# MainIC.net
KiCad netlist of a schematic drawn in Altium Designer
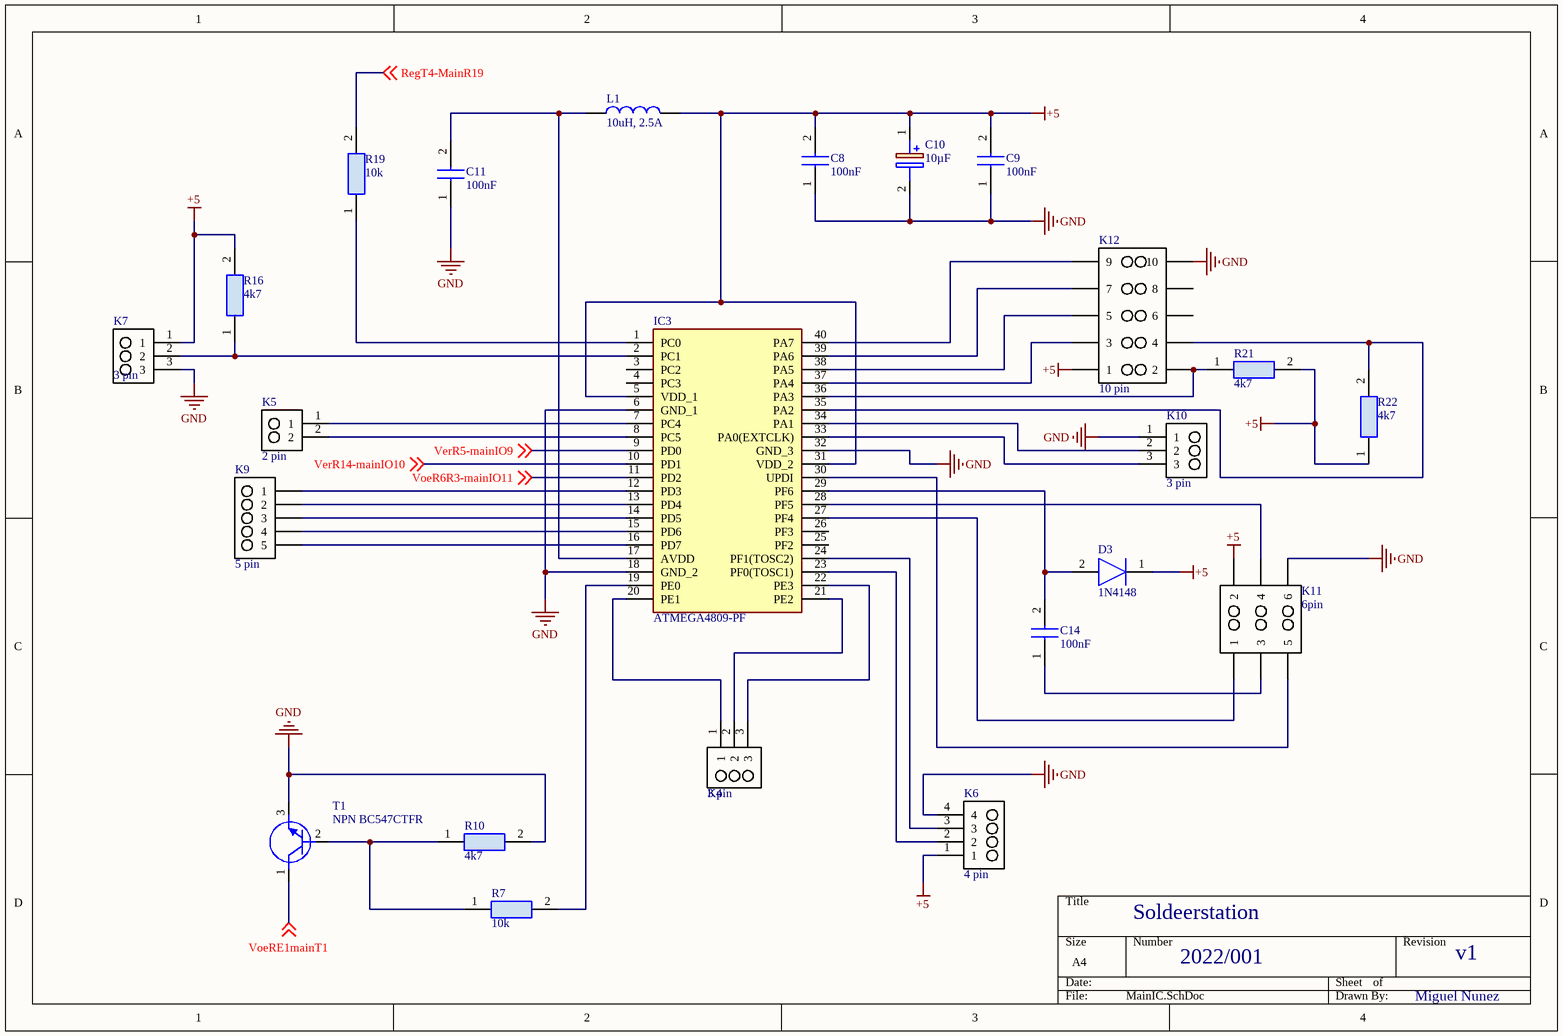
[diagram p0: MainIC.SchDoc]

(export (version "E")
  (design (tool "Eeschema 10.0.6"))
  (components
    (comp (ref "C8")
      (value "100nF")
      (footprint "WCAP-CSGP_0805_L2W1.25H0.8_Reflow")
      (description "Capacitor C0805C104K8RACAUTO")
      (fields (field (name "MANUFACTURER_PART_NUMBER") "C0805C104K8RACAUTO"))
      (libsource (lib "PO_SS_Lib") (part "CAP 0.1µF (100nF)"))
    )
    (comp (ref "C9")
      (value "100nF")
      (footprint "WCAP-CSGP_0805_L2W1.25H0.8_Reflow")
      (description "Capacitor C0805C104K8RACAUTO")
      (fields (field (name "MANUFACTURER_PART_NUMBER") "C0805C104K8RACAUTO"))
      (libsource (lib "PO_SS_Lib") (part "CAP 0.1µF (100nF)"))
    )
    (comp (ref "C10")
      (value "10µF")
      (footprint "WCAP-AT1H_D5H11")
      (description "Capacitor Polarised Wurth Elektronik 860240672002 10µF")
      (fields (field (name "MANUFACTURER_PART_NUMBER") "860240672002"))
      (libsource (lib "PO_SS_Lib") (part "ELCAP 10µF"))
    )
    (comp (ref "C11")
      (value "100nF")
      (footprint "WCAP-CSGP_0805_L2W1.25H0.8_Reflow")
      (description "Capacitor C0805C104K8RACAUTO")
      (fields (field (name "MANUFACTURER_PART_NUMBER") "C0805C104K8RACAUTO"))
      (libsource (lib "PO_SS_Lib") (part "CAP 0.1µF (100nF)"))
    )
    (comp (ref "C14")
      (value "100nF")
      (footprint "WCAP-CSGP_0805_L2W1.25H0.8_Reflow")
      (description "Capacitor C0805C104K8RACAUTO")
      (fields (field (name "MANUFACTURER_PART_NUMBER") "C0805C104K8RACAUTO"))
      (libsource (lib "PO_SS_Lib") (part "CAP 0.1µF (100nF)"))
    )
    (comp (ref "D3")
      (value "1N4148")
      (footprint "SamacSys:DIOAD1165W56L425D185")
      (description "Diode 1N4148 100V, 200mA")
      (libsource (lib "PO_SS_Lib") (part "D 1N4148"))
    )
    (comp (ref "IC3")
      (value "ATMEGA4809-PF")
      (footprint "SamacSys:DIP1543W58P254L5175H635Q40N")
      (description "Integrated Circuit")
      (fields (field (name "MOUSER2 PART NUMBER") "556-ATMEGA4809-PF"))
      (libsource (lib "PO_SS_Lib") (part "ATMEGA4809-PF"))
    )
    (comp (ref "K4")
      (value "3 pin")
      (footprint "691214310003")
      (description "Connector 61900311121 3 pin")
      (fields (field (name "MANUFACTURER_PART_NUMBER") "61900311121"))
      (libsource (lib "") (part "Header 1x3pin_2"))
    )
    (comp (ref "K5")
      (value "2 pin")
      (footprint "691214110002")
      (description "Connector 2 pin 212520-1002")
      (fields (field (name "MANUFACTURER_PART_NUMBER") "212520-1002"))
      (libsource (lib "PO_SS_Lib") (part "Header 1x2pin"))
    )
    (comp (ref "K6")
      (value "4 pin")
      (footprint "SHDR4W78P0X254_1X4_1026X252X700P")
      (description "Connector 216571-3004 1x4 pin")
      (fields (field (name "MANUFACTURER_PART_NUMBER") "216571-3004"))
      (libsource (lib "PO_SS_Lib") (part "Header 1x4pin"))
    )
    (comp (ref "K7")
      (value "3 pin")
      (footprint "691214310003")
      (description "Connector 61900311121 3 pin")
      (fields (field (name "MANUFACTURER_PART_NUMBER") "61900311121"))
      (libsource (lib "") (part "Header 1x3pin_1"))
    )
    (comp (ref "K9")
      (value "5 pin")
      (footprint "215297-5_TYC")
      (description "Header, 5-Pin")
      (fields (field (name "PUBLISHER") "Altium Limited"))
      (libsource (lib "PO_SS_Lib") (part "Header 1x 5pin"))
    )
    (comp (ref "K10")
      (value "3 pin")
      (footprint "691214310003")
      (description "Connector 61900311121 3 pin")
      (fields (field (name "MANUFACTURER_PART_NUMBER") "61900311121"))
      (libsource (lib "PO_SS_Lib") (part "Header 1x3pin"))
    )
    (comp (ref "K11")
      (value "6pin")
      (footprint "215307-3_TYC")
      (description "Header, 3-Pin, Dual row")
      (fields (field (name "PUBLISHER") "Altium Limited"))
      (libsource (lib "PO_SS_Lib") (part "Header 2x3"))
    )
    (comp (ref "K12")
      (value "10 pin")
      (footprint "215307-5_TYC")
      (description "Header, 5-Pin, Dual row")
      (fields (field (name "PUBLISHER") "Altium Limited"))
      (libsource (lib "PO_SS_Lib") (part "Header 2x5"))
    )
    (comp (ref "L1")
      (value "10uH, 2.5A")
      (footprint "744711003")
      (description "WE-SD THT Rod Core Choke, 10uH, 2.5A  744711003")
      (fields
        (field (name "MANUFACTURER PART NUMBER") "744711003")
        (field (name "MANUFACTURER") "Wurth Elektronik")
      )
      (libsource (lib "PO_SS_Lib") (part "spoel WE klein"))
    )
    (comp (ref "R7")
      (value "10k")
      (footprint "SamacSys:RESC2012X60N")
      (description "10k SMD 0805  CR0805-FX-1002ELF")
      (fields
        (field (name "MOUSER2 PART NUMBER") "652-CR0805FX-1002ELF")
        (field (name "MANUFACTURER_PART_NUMBER") "CR0805-FX-1002ELF")
      )
      (libsource (lib "") (part "RES 10k 0805_1"))
    )
    (comp (ref "R10")
      (value "4k7")
      (footprint "SamacSys:CAPC2012X65N")
      (description "4k7 SMD 0805  ESR10EZPJ472")
      (fields (field (name "MANUFACTURER_PART_NUMBER") "ESR10EZPJ472"))
      (libsource (lib "") (part "RES 4k7 0805_1"))
    )
    (comp (ref "R16")
      (value "4k7")
      (footprint "SamacSys:CAPC2012X65N")
      (description "4k7 SMD 0805  ESR10EZPJ472")
      (fields (field (name "MANUFACTURER_PART_NUMBER") "ESR10EZPJ472"))
      (libsource (lib "PO_SS_Lib") (part "RES 4k7 0805"))
    )
    (comp (ref "R19")
      (value "10k")
      (footprint "SamacSys:RESC2012X60N")
      (description "10k SMD 0805  CR0805-FX-1002ELF")
      (fields
        (field (name "MOUSER2 PART NUMBER") "652-CR0805FX-1002ELF")
        (field (name "MANUFACTURER_PART_NUMBER") "CR0805-FX-1002ELF")
      )
      (libsource (lib "PO_SS_Lib") (part "RES 10k 0805"))
    )
    (comp (ref "R21")
      (value "4k7")
      (footprint "SamacSys:CAPC2012X65N")
      (description "4k7 SMD 0805  ESR10EZPJ472")
      (fields (field (name "MANUFACTURER_PART_NUMBER") "ESR10EZPJ472"))
      (libsource (lib "") (part "RES 4k7 0805_1"))
    )
    (comp (ref "R22")
      (value "4k7")
      (footprint "SamacSys:CAPC2012X65N")
      (description "4k7 SMD 0805  ESR10EZPJ472")
      (fields (field (name "MANUFACTURER_PART_NUMBER") "ESR10EZPJ472"))
      (libsource (lib "PO_SS_Lib") (part "RES 4k7 0805"))
    )
    (comp (ref "T1")
      (value "NPN BC547CTFR")
      (footprint "BC33740TA")
      (description "Transistor BC547CTFR NPN")
      (fields
        (field (name "MANUFACTURER_PART_NUMBER") "BC547CTFR")
        (field (name "COPYRIGHT") "Copyright (C) 2022 Ultra Librarian. All rights reserved.")
      )
      (libsource (lib "PO_SS_Lib") (part "TR BC547CTFR"))
    )
  )
  (nets
    (net (code "1") (name "+5") (class "Default")
      (node (ref "C10") (pin "1") (pinfunction "+_1") (pintype "passive"))
      (node (ref "C8") (pin "2") (pinfunction "2_2") (pintype "passive"))
      (node (ref "C9") (pin "2") (pinfunction "2_2") (pintype "passive"))
      (node (ref "D3") (pin "1") (pinfunction "K_1") (pintype "passive"))
      (node (ref "IC3") (pin "31") (pinfunction "VDD_2_31") (pintype "passive"))
      (node (ref "IC3") (pin "5") (pinfunction "VDD_1_5") (pintype "passive"))
      (node (ref "K11") (pin "2") (pinfunction "2_2") (pintype "passive"))
      (node (ref "K12") (pin "1") (pinfunction "1_1") (pintype "passive"))
      (node (ref "K6") (pin "1") (pinfunction "1_1") (pintype "passive"))
      (node (ref "K7") (pin "1") (pinfunction "1_1") (pintype "passive"))
      (node (ref "L1") (pin "2") (pinfunction "2_2") (pintype "passive"))
      (node (ref "R16") (pin "2") (pinfunction "2_2") (pintype "passive"))
      (node (ref "R21") (pin "2") (pinfunction "2_2") (pintype "passive"))
      (node (ref "R22") (pin "1") (pinfunction "1_1") (pintype "passive"))
    )
    (net (code "2") (name "GND") (class "Default")
      (node (ref "C10") (pin "2") (pinfunction "-_2") (pintype "passive"))
      (node (ref "C11") (pin "1") (pinfunction "1_1") (pintype "passive"))
      (node (ref "C8") (pin "1") (pinfunction "1_1") (pintype "passive"))
      (node (ref "C9") (pin "1") (pinfunction "1_1") (pintype "passive"))
      (node (ref "IC3") (pin "18") (pinfunction "GND_2_18") (pintype "passive"))
      (node (ref "IC3") (pin "32") (pinfunction "GND_3_32") (pintype "passive"))
      (node (ref "IC3") (pin "6") (pinfunction "GND_1_6") (pintype "passive"))
      (node (ref "K10") (pin "1") (pinfunction "1_1") (pintype "passive"))
      (node (ref "K11") (pin "6") (pinfunction "6_6") (pintype "passive"))
      (node (ref "K12") (pin "10") (pinfunction "10_10") (pintype "passive"))
      (node (ref "K6") (pin "4") (pinfunction "4_4") (pintype "passive"))
      (node (ref "K7") (pin "3") (pinfunction "3_3") (pintype "passive"))
      (node (ref "R10") (pin "2") (pinfunction "2_2") (pintype "passive"))
      (node (ref "T1") (pin "3") (pinfunction "E_3") (pintype "passive"))
    )
    (net (code "3") (name "Net-(C14-Pad1)") (class "Default")
      (node (ref "C14") (pin "1") (pinfunction "1_1") (pintype "passive"))
      (node (ref "K11") (pin "3") (pinfunction "3_3") (pintype "passive"))
    )
    (net (code "4") (name "Net-(D3-A)") (class "Default")
      (node (ref "C14") (pin "2") (pinfunction "2_2") (pintype "passive"))
      (node (ref "D3") (pin "2") (pinfunction "A_2") (pintype "passive"))
      (node (ref "IC3") (pin "29") (pinfunction "PF6_29") (pintype "passive"))
    )
    (net (code "5") (name "Net-(IC3-AVDD)") (class "Default")
      (node (ref "C11") (pin "2") (pinfunction "2_2") (pintype "passive"))
      (node (ref "IC3") (pin "17") (pinfunction "AVDD_17") (pintype "passive"))
      (node (ref "L1") (pin "1") (pinfunction "1_1") (pintype "passive"))
    )
    (net (code "6") (name "Net-(IC3-PA0(EXTCLK))") (class "Default")
      (node (ref "IC3") (pin "33") (pinfunction "PA0(EXTCLK)_33") (pintype "passive"))
      (node (ref "K10") (pin "3") (pinfunction "3_3") (pintype "passive"))
    )
    (net (code "7") (name "Net-(IC3-PA1)") (class "Default")
      (node (ref "IC3") (pin "34") (pinfunction "PA1_34") (pintype "passive"))
      (node (ref "K10") (pin "2") (pinfunction "2_2") (pintype "passive"))
    )
    (net (code "8") (name "Net-(IC3-PA2)") (class "Default")
      (node (ref "IC3") (pin "35") (pinfunction "PA2_35") (pintype "passive"))
      (node (ref "K12") (pin "4") (pinfunction "4_4") (pintype "passive"))
      (node (ref "R22") (pin "2") (pinfunction "2_2") (pintype "passive"))
    )
    (net (code "9") (name "Net-(IC3-PA3)") (class "Default")
      (node (ref "IC3") (pin "36") (pinfunction "PA3_36") (pintype "passive"))
      (node (ref "K12") (pin "2") (pinfunction "2_2") (pintype "passive"))
      (node (ref "R21") (pin "1") (pinfunction "1_1") (pintype "passive"))
    )
    (net (code "10") (name "Net-(IC3-PA4)") (class "Default")
      (node (ref "IC3") (pin "37") (pinfunction "PA4_37") (pintype "passive"))
      (node (ref "K12") (pin "3") (pinfunction "3_3") (pintype "passive"))
    )
    (net (code "11") (name "Net-(IC3-PA5)") (class "Default")
      (node (ref "IC3") (pin "38") (pinfunction "PA5_38") (pintype "passive"))
      (node (ref "K12") (pin "5") (pinfunction "5_5") (pintype "passive"))
    )
    (net (code "12") (name "Net-(IC3-PA6)") (class "Default")
      (node (ref "IC3") (pin "39") (pinfunction "PA6_39") (pintype "passive"))
      (node (ref "K12") (pin "7") (pinfunction "7_7") (pintype "passive"))
    )
    (net (code "13") (name "Net-(IC3-PA7)") (class "Default")
      (node (ref "IC3") (pin "40") (pinfunction "PA7_40") (pintype "passive"))
      (node (ref "K12") (pin "9") (pinfunction "9_9") (pintype "passive"))
    )
    (net (code "14") (name "Net-(IC3-PC0)") (class "Default")
      (node (ref "IC3") (pin "1") (pinfunction "PC0_1") (pintype "passive"))
      (node (ref "R19") (pin "1") (pinfunction "1_1") (pintype "passive"))
    )
    (net (code "15") (name "Net-(IC3-PC1)") (class "Default")
      (node (ref "IC3") (pin "2") (pinfunction "PC1_2") (pintype "passive"))
      (node (ref "K7") (pin "2") (pinfunction "2_2") (pintype "passive"))
      (node (ref "R16") (pin "1") (pinfunction "1_1") (pintype "passive"))
    )
    (net (code "16") (name "Net-(IC3-PC4)") (class "Default")
      (node (ref "IC3") (pin "7") (pinfunction "PC4_7") (pintype "passive"))
      (node (ref "K5") (pin "1") (pinfunction "1_1") (pintype "passive"))
    )
    (net (code "17") (name "Net-(IC3-PC5)") (class "Default")
      (node (ref "IC3") (pin "8") (pinfunction "PC5_8") (pintype "passive"))
      (node (ref "K5") (pin "2") (pinfunction "2_2") (pintype "passive"))
    )
    (net (code "18") (name "Net-(IC3-PD3)") (class "Default")
      (node (ref "IC3") (pin "12") (pinfunction "PD3_12") (pintype "passive"))
      (node (ref "K9") (pin "1") (pinfunction "1_1") (pintype "passive"))
    )
    (net (code "19") (name "Net-(IC3-PD4)") (class "Default")
      (node (ref "IC3") (pin "13") (pinfunction "PD4_13") (pintype "passive"))
      (node (ref "K9") (pin "2") (pinfunction "2_2") (pintype "passive"))
    )
    (net (code "20") (name "Net-(IC3-PD5)") (class "Default")
      (node (ref "IC3") (pin "14") (pinfunction "PD5_14") (pintype "passive"))
      (node (ref "K9") (pin "3") (pinfunction "3_3") (pintype "passive"))
    )
    (net (code "21") (name "Net-(IC3-PD6)") (class "Default")
      (node (ref "IC3") (pin "15") (pinfunction "PD6_15") (pintype "passive"))
      (node (ref "K9") (pin "4") (pinfunction "4_4") (pintype "passive"))
    )
    (net (code "22") (name "Net-(IC3-PD7)") (class "Default")
      (node (ref "IC3") (pin "16") (pinfunction "PD7_16") (pintype "passive"))
      (node (ref "K9") (pin "5") (pinfunction "5_5") (pintype "passive"))
    )
    (net (code "23") (name "Net-(IC3-PE0)") (class "Default")
      (node (ref "IC3") (pin "19") (pinfunction "PE0_19") (pintype "passive"))
      (node (ref "R7") (pin "2") (pinfunction "2_2") (pintype "passive"))
    )
    (net (code "24") (name "Net-(IC3-PE1)") (class "Default")
      (node (ref "IC3") (pin "20") (pinfunction "PE1_20") (pintype "passive"))
      (node (ref "K4") (pin "1") (pinfunction "1_1") (pintype "passive"))
    )
    (net (code "25") (name "Net-(IC3-PE2)") (class "Default")
      (node (ref "IC3") (pin "21") (pinfunction "PE2_21") (pintype "passive"))
      (node (ref "K4") (pin "2") (pinfunction "2_2") (pintype "passive"))
    )
    (net (code "26") (name "Net-(IC3-PE3)") (class "Default")
      (node (ref "IC3") (pin "22") (pinfunction "PE3_22") (pintype "passive"))
      (node (ref "K4") (pin "3") (pinfunction "3_3") (pintype "passive"))
    )
    (net (code "27") (name "Net-(IC3-PF0(TOSC1))") (class "Default")
      (node (ref "IC3") (pin "23") (pinfunction "PF0(TOSC1)_23") (pintype "passive"))
      (node (ref "K6") (pin "2") (pinfunction "2_2") (pintype "passive"))
    )
    (net (code "28") (name "Net-(IC3-PF1(TOSC2))") (class "Default")
      (node (ref "IC3") (pin "24") (pinfunction "PF1(TOSC2)_24") (pintype "passive"))
      (node (ref "K6") (pin "3") (pinfunction "3_3") (pintype "passive"))
    )
    (net (code "29") (name "Net-(IC3-PF4)") (class "Default")
      (node (ref "IC3") (pin "27") (pinfunction "PF4_27") (pintype "passive"))
      (node (ref "K11") (pin "1") (pinfunction "1_1") (pintype "passive"))
    )
    (net (code "30") (name "Net-(IC3-PF5)") (class "Default")
      (node (ref "IC3") (pin "28") (pinfunction "PF5_28") (pintype "passive"))
      (node (ref "K11") (pin "4") (pinfunction "4_4") (pintype "passive"))
    )
    (net (code "31") (name "Net-(IC3-UPDI)") (class "Default")
      (node (ref "IC3") (pin "30") (pinfunction "UPDI_30") (pintype "passive"))
      (node (ref "K11") (pin "5") (pinfunction "5_5") (pintype "passive"))
    )
    (net (code "32") (name "Net-(T1-B)") (class "Default")
      (node (ref "R10") (pin "1") (pinfunction "1_1") (pintype "passive"))
      (node (ref "R7") (pin "1") (pinfunction "1_1") (pintype "passive"))
      (node (ref "T1") (pin "2") (pinfunction "B_2") (pintype "passive"))
    )
    (net (code "33") (name "RegT4-MainR19") (class "Default")
      (node (ref "R19") (pin "2") (pinfunction "2_2") (pintype "passive"))
    )
    (net (code "34") (name "VerR5-mainIO9") (class "Default")
      (node (ref "IC3") (pin "9") (pinfunction "PD0_9") (pintype "passive"))
    )
    (net (code "35") (name "VerR14-mainIO10") (class "Default")
      (node (ref "IC3") (pin "10") (pinfunction "PD1_10") (pintype "passive"))
    )
    (net (code "36") (name "VoeR6R3-mainIO11") (class "Default")
      (node (ref "IC3") (pin "11") (pinfunction "PD2_11") (pintype "passive"))
    )
    (net (code "37") (name "VoeRE1mainT1") (class "Default")
      (node (ref "T1") (pin "1") (pinfunction "C_1") (pintype "passive"))
    )
    (net (code "38") (name "unconnected-(IC3-PC2-Pad3)") (class "Default")
      (node (ref "IC3") (pin "3") (pinfunction "PC2_3") (pintype "passive"))
    )
    (net (code "39") (name "unconnected-(IC3-PC3-Pad4)") (class "Default")
      (node (ref "IC3") (pin "4") (pinfunction "PC3_4") (pintype "passive"))
    )
    (net (code "40") (name "unconnected-(IC3-PF2-Pad25)") (class "Default")
      (node (ref "IC3") (pin "25") (pinfunction "PF2_25") (pintype "passive"))
    )
    (net (code "41") (name "unconnected-(IC3-PF3-Pad26)") (class "Default")
      (node (ref "IC3") (pin "26") (pinfunction "PF3_26") (pintype "passive"))
    )
    (net (code "42") (name "unconnected-(K12-Pad6)") (class "Default")
      (node (ref "K12") (pin "6") (pinfunction "6_6") (pintype "passive"))
    )
    (net (code "43") (name "unconnected-(K12-Pad8)") (class "Default")
      (node (ref "K12") (pin "8") (pinfunction "8_8") (pintype "passive"))
    )
  )
)
